# Button_Connections.net
KiCad netlist of a schematic drawn in EAGLE
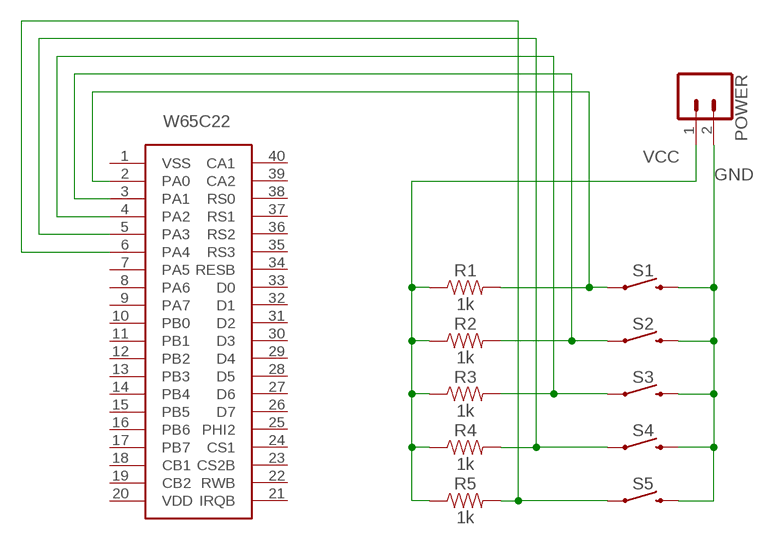
[diagram p0: schematic, sheet 1]

(export (version "E")
  (design (tool "Eeschema 10.0.6"))
  (components
    (comp (ref "POWER")
      (value "CONN_02POGO_PIN_HOLES_ONLY")
      (footprint "eagle-import:1X02_PP_HOLES_ONLY")
      (libsource (lib "eagle-import") (part "CONN_02POGO_PIN_HOLES_ONLY"))
    )
    (comp (ref "R1")
      (value "1k")
      (footprint "eagle-import:AXIAL-0.3")
      (libsource (lib "eagle-import") (part "1KOHM-HORIZ-1/4W-5%"))
    )
    (comp (ref "R2")
      (value "1k")
      (footprint "eagle-import:AXIAL-0.3")
      (libsource (lib "eagle-import") (part "1KOHM-HORIZ-1/4W-5%"))
    )
    (comp (ref "R3")
      (value "1k")
      (footprint "eagle-import:AXIAL-0.3")
      (libsource (lib "eagle-import") (part "1KOHM-HORIZ-1/4W-5%"))
    )
    (comp (ref "R4")
      (value "1k")
      (footprint "eagle-import:AXIAL-0.3")
      (libsource (lib "eagle-import") (part "1KOHM-HORIZ-1/4W-5%"))
    )
    (comp (ref "R5")
      (value "1k")
      (footprint "eagle-import:AXIAL-0.3")
      (libsource (lib "eagle-import") (part "1KOHM-HORIZ-1/4W-5%"))
    )
    (comp (ref "S1")
      (value "MOMENTARY-SWITCH-SPST-PTH-6.0MM")
      (footprint "eagle-import:TACTILE_SWITCH_PTH_6.0MM")
      (libsource (lib "eagle-import") (part "MOMENTARY-SWITCH-SPST-PTH-6.0MM"))
    )
    (comp (ref "S2")
      (value "MOMENTARY-SWITCH-SPST-PTH-6.0MM")
      (footprint "eagle-import:TACTILE_SWITCH_PTH_6.0MM")
      (libsource (lib "eagle-import") (part "MOMENTARY-SWITCH-SPST-PTH-6.0MM"))
    )
    (comp (ref "S3")
      (value "MOMENTARY-SWITCH-SPST-PTH-6.0MM")
      (footprint "eagle-import:TACTILE_SWITCH_PTH_6.0MM")
      (libsource (lib "eagle-import") (part "MOMENTARY-SWITCH-SPST-PTH-6.0MM"))
    )
    (comp (ref "S4")
      (value "MOMENTARY-SWITCH-SPST-PTH-6.0MM")
      (footprint "eagle-import:TACTILE_SWITCH_PTH_6.0MM")
      (libsource (lib "eagle-import") (part "MOMENTARY-SWITCH-SPST-PTH-6.0MM"))
    )
    (comp (ref "S5")
      (value "MOMENTARY-SWITCH-SPST-PTH-6.0MM")
      (footprint "eagle-import:TACTILE_SWITCH_PTH_6.0MM")
      (libsource (lib "eagle-import") (part "MOMENTARY-SWITCH-SPST-PTH-6.0MM"))
    )
    (comp (ref "U$1")
      (value "W65C22")
      (footprint "eagle-import:DIP1150W53P250L4975H200Q40B")
      (libsource (lib "eagle-import") (part "W65C22"))
    )
  )
  (nets
    (net (code "1") (name "/GND") (class "Default")
      (node (ref "POWER") (pin "2") (pinfunction "2_2") (pintype "passive"))
      (node (ref "S1") (pin "3") (pinfunction "2_3") (pintype "passive"))
      (node (ref "S2") (pin "3") (pinfunction "2_3") (pintype "passive"))
      (node (ref "S3") (pin "3") (pinfunction "2_3") (pintype "passive"))
      (node (ref "S4") (pin "3") (pinfunction "2_3") (pintype "passive"))
      (node (ref "S5") (pin "3") (pinfunction "2_3") (pintype "passive"))
    )
    (net (code "2") (name "/VCC") (class "Default")
      (node (ref "POWER") (pin "1") (pinfunction "1_1") (pintype "passive"))
      (node (ref "R1") (pin "P$1") (pinfunction "1_P$1") (pintype "passive"))
      (node (ref "R2") (pin "P$1") (pinfunction "1_P$1") (pintype "passive"))
      (node (ref "R3") (pin "P$1") (pinfunction "1_P$1") (pintype "passive"))
      (node (ref "R4") (pin "P$1") (pinfunction "1_P$1") (pintype "passive"))
      (node (ref "R5") (pin "P$1") (pinfunction "1_P$1") (pintype "passive"))
    )
    (net (code "3") (name "Net-(R1-2)") (class "Default")
      (node (ref "R1") (pin "P$2") (pinfunction "2_P$2") (pintype "passive"))
      (node (ref "S1") (pin "1") (pinfunction "1_1") (pintype "passive"))
      (node (ref "U$1") (pin "2") (pinfunction "PA0_2") (pintype "bidirectional"))
    )
    (net (code "4") (name "Net-(R2-2)") (class "Default")
      (node (ref "R2") (pin "P$2") (pinfunction "2_P$2") (pintype "passive"))
      (node (ref "S2") (pin "1") (pinfunction "1_1") (pintype "passive"))
      (node (ref "U$1") (pin "3") (pinfunction "PA1_3") (pintype "bidirectional"))
    )
    (net (code "5") (name "Net-(R3-2)") (class "Default")
      (node (ref "R3") (pin "P$2") (pinfunction "2_P$2") (pintype "passive"))
      (node (ref "S3") (pin "1") (pinfunction "1_1") (pintype "passive"))
      (node (ref "U$1") (pin "4") (pinfunction "PA2_4") (pintype "bidirectional"))
    )
    (net (code "6") (name "Net-(R4-2)") (class "Default")
      (node (ref "R4") (pin "P$2") (pinfunction "2_P$2") (pintype "passive"))
      (node (ref "S4") (pin "1") (pinfunction "1_1") (pintype "passive"))
      (node (ref "U$1") (pin "5") (pinfunction "PA3_5") (pintype "bidirectional"))
    )
    (net (code "7") (name "Net-(R5-2)") (class "Default")
      (node (ref "R5") (pin "P$2") (pinfunction "2_P$2") (pintype "passive"))
      (node (ref "S5") (pin "1") (pinfunction "1_1") (pintype "passive"))
      (node (ref "U$1") (pin "6") (pinfunction "PA4_6") (pintype "bidirectional"))
    )
    (net (code "8") (name "unconnected-(U$1-CA1-Pad40)") (class "Default")
      (node (ref "U$1") (pin "40") (pinfunction "CA1_40") (pintype "bidirectional"))
    )
    (net (code "9") (name "unconnected-(U$1-CA2-Pad39)") (class "Default")
      (node (ref "U$1") (pin "39") (pinfunction "CA2_39") (pintype "bidirectional"))
    )
    (net (code "10") (name "unconnected-(U$1-CB1-Pad18)") (class "Default")
      (node (ref "U$1") (pin "18") (pinfunction "CB1_18") (pintype "bidirectional"))
    )
    (net (code "11") (name "unconnected-(U$1-CB2-Pad19)") (class "Default")
      (node (ref "U$1") (pin "19") (pinfunction "CB2_19") (pintype "bidirectional"))
    )
    (net (code "12") (name "unconnected-(U$1-CS1-Pad24)") (class "Default")
      (node (ref "U$1") (pin "24") (pinfunction "CS1_24") (pintype "bidirectional"))
    )
    (net (code "13") (name "unconnected-(U$1-CS2B-Pad23)") (class "Default")
      (node (ref "U$1") (pin "23") (pinfunction "CS2B_23") (pintype "bidirectional"))
    )
    (net (code "14") (name "unconnected-(U$1-D0-Pad33)") (class "Default")
      (node (ref "U$1") (pin "33") (pinfunction "D0_33") (pintype "bidirectional"))
    )
    (net (code "15") (name "unconnected-(U$1-D1-Pad32)") (class "Default")
      (node (ref "U$1") (pin "32") (pinfunction "D1_32") (pintype "bidirectional"))
    )
    (net (code "16") (name "unconnected-(U$1-D2-Pad31)") (class "Default")
      (node (ref "U$1") (pin "31") (pinfunction "D2_31") (pintype "bidirectional"))
    )
    (net (code "17") (name "unconnected-(U$1-D3-Pad30)") (class "Default")
      (node (ref "U$1") (pin "30") (pinfunction "D3_30") (pintype "bidirectional"))
    )
    (net (code "18") (name "unconnected-(U$1-D4-Pad29)") (class "Default")
      (node (ref "U$1") (pin "29") (pinfunction "D4_29") (pintype "bidirectional"))
    )
    (net (code "19") (name "unconnected-(U$1-D5-Pad28)") (class "Default")
      (node (ref "U$1") (pin "28") (pinfunction "D5_28") (pintype "bidirectional"))
    )
    (net (code "20") (name "unconnected-(U$1-D6-Pad27)") (class "Default")
      (node (ref "U$1") (pin "27") (pinfunction "D6_27") (pintype "bidirectional"))
    )
    (net (code "21") (name "unconnected-(U$1-D7-Pad26)") (class "Default")
      (node (ref "U$1") (pin "26") (pinfunction "D7_26") (pintype "bidirectional"))
    )
    (net (code "22") (name "unconnected-(U$1-IRQB-Pad21)") (class "Default")
      (node (ref "U$1") (pin "21") (pinfunction "IRQB_21") (pintype "bidirectional"))
    )
    (net (code "23") (name "unconnected-(U$1-PA5-Pad7)") (class "Default")
      (node (ref "U$1") (pin "7") (pinfunction "PA5_7") (pintype "bidirectional"))
    )
    (net (code "24") (name "unconnected-(U$1-PA6-Pad8)") (class "Default")
      (node (ref "U$1") (pin "8") (pinfunction "PA6_8") (pintype "bidirectional"))
    )
    (net (code "25") (name "unconnected-(U$1-PA7-Pad9)") (class "Default")
      (node (ref "U$1") (pin "9") (pinfunction "PA7_9") (pintype "bidirectional"))
    )
    (net (code "26") (name "unconnected-(U$1-PB0-Pad10)") (class "Default")
      (node (ref "U$1") (pin "10") (pinfunction "PB0_10") (pintype "bidirectional"))
    )
    (net (code "27") (name "unconnected-(U$1-PB1-Pad11)") (class "Default")
      (node (ref "U$1") (pin "11") (pinfunction "PB1_11") (pintype "bidirectional"))
    )
    (net (code "28") (name "unconnected-(U$1-PB2-Pad12)") (class "Default")
      (node (ref "U$1") (pin "12") (pinfunction "PB2_12") (pintype "bidirectional"))
    )
    (net (code "29") (name "unconnected-(U$1-PB3-Pad13)") (class "Default")
      (node (ref "U$1") (pin "13") (pinfunction "PB3_13") (pintype "bidirectional"))
    )
    (net (code "30") (name "unconnected-(U$1-PB4-Pad14)") (class "Default")
      (node (ref "U$1") (pin "14") (pinfunction "PB4_14") (pintype "bidirectional"))
    )
    (net (code "31") (name "unconnected-(U$1-PB5-Pad15)") (class "Default")
      (node (ref "U$1") (pin "15") (pinfunction "PB5_15") (pintype "bidirectional"))
    )
    (net (code "32") (name "unconnected-(U$1-PB6-Pad16)") (class "Default")
      (node (ref "U$1") (pin "16") (pinfunction "PB6_16") (pintype "bidirectional"))
    )
    (net (code "33") (name "unconnected-(U$1-PB7-Pad17)") (class "Default")
      (node (ref "U$1") (pin "17") (pinfunction "PB7_17") (pintype "bidirectional"))
    )
    (net (code "34") (name "unconnected-(U$1-PHI2-Pad25)") (class "Default")
      (node (ref "U$1") (pin "25") (pinfunction "PHI2_25") (pintype "bidirectional"))
    )
    (net (code "35") (name "unconnected-(U$1-RESB-Pad34)") (class "Default")
      (node (ref "U$1") (pin "34") (pinfunction "RESB_34") (pintype "bidirectional"))
    )
    (net (code "36") (name "unconnected-(U$1-RS0-Pad38)") (class "Default")
      (node (ref "U$1") (pin "38") (pinfunction "RS0_38") (pintype "bidirectional"))
    )
    (net (code "37") (name "unconnected-(U$1-RS1-Pad37)") (class "Default")
      (node (ref "U$1") (pin "37") (pinfunction "RS1_37") (pintype "bidirectional"))
    )
    (net (code "38") (name "unconnected-(U$1-RS2-Pad36)") (class "Default")
      (node (ref "U$1") (pin "36") (pinfunction "RS2_36") (pintype "bidirectional"))
    )
    (net (code "39") (name "unconnected-(U$1-RS3-Pad35)") (class "Default")
      (node (ref "U$1") (pin "35") (pinfunction "RS3_35") (pintype "bidirectional"))
    )
    (net (code "40") (name "unconnected-(U$1-RWB-Pad22)") (class "Default")
      (node (ref "U$1") (pin "22") (pinfunction "RWB_22") (pintype "bidirectional"))
    )
    (net (code "41") (name "unconnected-(U$1-VDD-Pad20)") (class "Default")
      (node (ref "U$1") (pin "20") (pinfunction "VDD_20") (pintype "bidirectional"))
    )
    (net (code "42") (name "unconnected-(U$1-VSS-Pad1)") (class "Default")
      (node (ref "U$1") (pin "1") (pinfunction "VSS_1") (pintype "bidirectional"))
    )
  )
)
